# DMIC_LED.net
KiCad netlist of a schematic drawn in Altium Designer
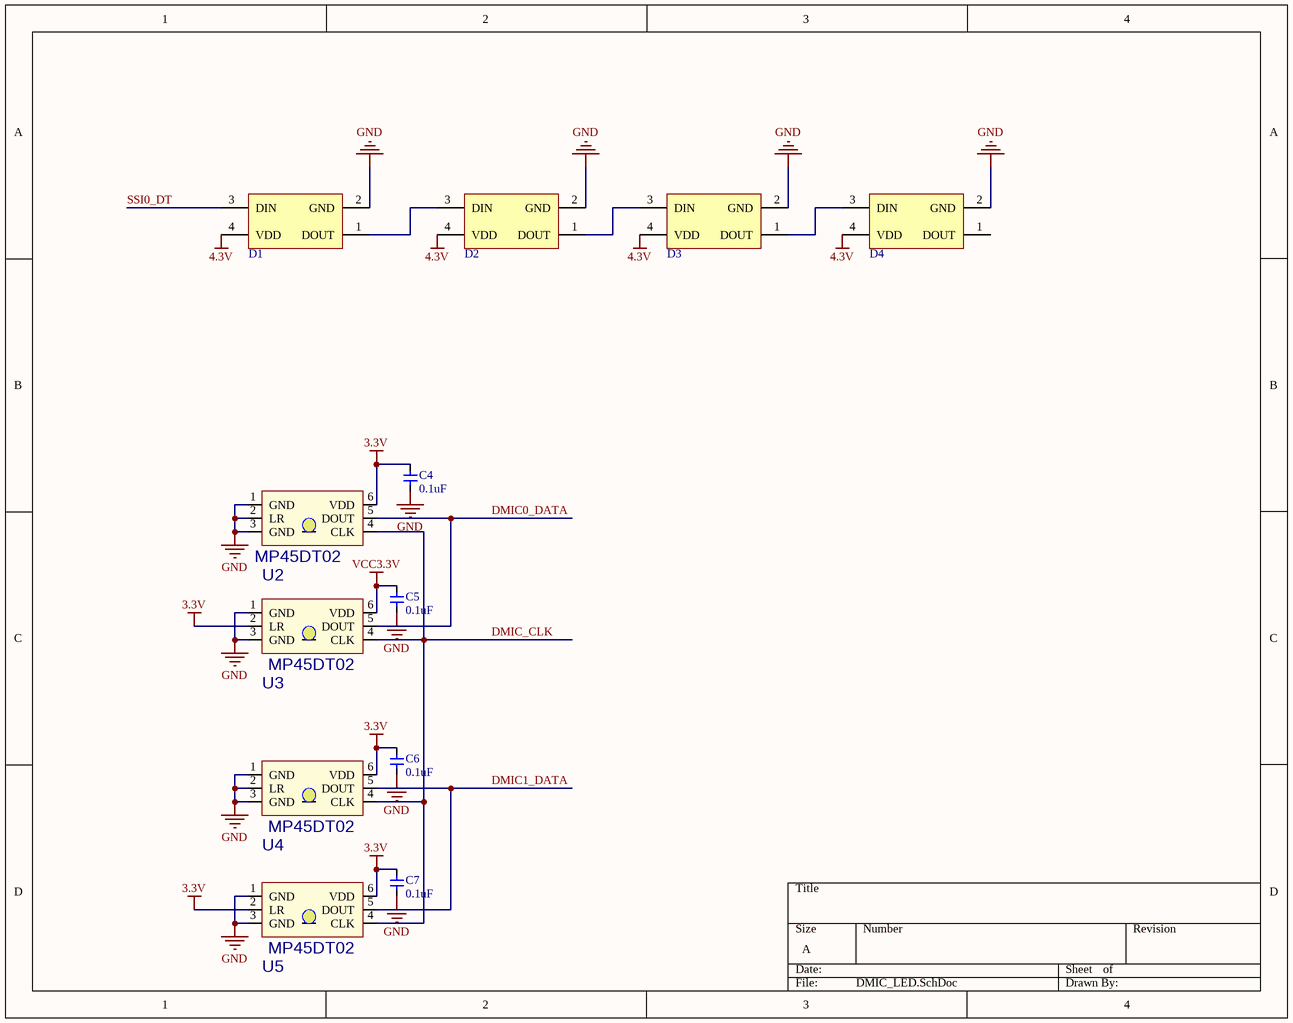
[diagram p0: DMIC_LED.SchDoc]

(export (version "E")
  (design (tool "Eeschema 10.0.6"))
  (components
    (comp (ref "C4")
      (value "0.1uF")
      (footprint "PCB_PassiveCap:CAP_0603")
      (description "Capacitor")
      (fields (field (name "Comment") "Cap_0603"))
      (libsource (lib "SCH_Passive") (part "Cap_0603"))
    )
    (comp (ref "C5")
      (value "0.1uF")
      (footprint "PCB_PassiveCap:CAP_0603")
      (description "Capacitor")
      (fields (field (name "Comment") "Cap_0603"))
      (libsource (lib "SCH_Passive") (part "Cap_0603"))
    )
    (comp (ref "C6")
      (value "0.1uF")
      (footprint "PCB_PassiveCap:CAP_0603")
      (description "Capacitor")
      (fields (field (name "Comment") "Cap_0603"))
      (libsource (lib "SCH_Passive") (part "Cap_0603"))
    )
    (comp (ref "C7")
      (value "0.1uF")
      (footprint "PCB_PassiveCap:CAP_0603")
      (description "Capacitor")
      (fields (field (name "Comment") "Cap_0603"))
      (libsource (lib "SCH_Passive") (part "Cap_0603"))
    )
    (comp (ref "D1")
      (value "LED_3535_SK6812")
      (footprint "PCB_ActiveLED:LED_3535_4P")
      (description "LED")
      (libsource (lib "SCH_Active") (part "LED_3535_SK6812"))
    )
    (comp (ref "D2")
      (value "LED_3535_SK6812")
      (footprint "PCB_ActiveLED:LED_3535_4P")
      (description "LED")
      (libsource (lib "SCH_Active") (part "LED_3535_SK6812"))
    )
    (comp (ref "D3")
      (value "LED_3535_SK6812")
      (footprint "PCB_ActiveLED:LED_3535_4P")
      (description "LED")
      (libsource (lib "SCH_Active") (part "LED_3535_SK6812"))
    )
    (comp (ref "D4")
      (value "LED_3535_SK6812")
      (footprint "PCB_ActiveLED:LED_3535_4P")
      (description "LED")
      (libsource (lib "SCH_Active") (part "LED_3535_SK6812"))
    )
    (comp (ref "U2")
      (value "MP45DT02")
      (footprint "ST_HLGA6")
      (description "Mic Omni-Directional -26dB 3.6V Rectangular Solder Pad")
      (fields (field (name "MF") "STMicroelectronics"))
      (libsource (lib "SCH_IntegratedCircuit") (part "MP45DT02"))
    )
    (comp (ref "U3")
      (value "MP45DT02")
      (footprint "ST_HLGA6")
      (description "Mic Omni-Directional -26dB 3.6V Rectangular Solder Pad")
      (fields (field (name "MF") "STMicroelectronics"))
      (libsource (lib "SCH_IntegratedCircuit") (part "MP45DT02"))
    )
    (comp (ref "U4")
      (value "MP45DT02")
      (footprint "ST_HLGA6")
      (description "Mic Omni-Directional -26dB 3.6V Rectangular Solder Pad")
      (fields (field (name "MF") "STMicroelectronics"))
      (libsource (lib "SCH_IntegratedCircuit") (part "MP45DT02"))
    )
    (comp (ref "U5")
      (value "MP45DT02")
      (footprint "ST_HLGA6")
      (description "Mic Omni-Directional -26dB 3.6V Rectangular Solder Pad")
      (fields (field (name "MF") "STMicroelectronics"))
      (libsource (lib "SCH_IntegratedCircuit") (part "MP45DT02"))
    )
  )
  (nets
    (net (code "1") (name "/DMIC0_DATA") (class "Default")
      (node (ref "U2") (pin "5") (pinfunction "DOUT_5") (pintype "passive"))
      (node (ref "U3") (pin "5") (pinfunction "DOUT_5") (pintype "passive"))
    )
    (net (code "2") (name "/DMIC1_DATA") (class "Default")
      (node (ref "U4") (pin "5") (pinfunction "DOUT_5") (pintype "passive"))
      (node (ref "U5") (pin "5") (pinfunction "DOUT_5") (pintype "passive"))
    )
    (net (code "3") (name "/DMIC_CLK") (class "Default")
      (node (ref "U2") (pin "4") (pinfunction "CLK_4") (pintype "passive"))
      (node (ref "U3") (pin "4") (pinfunction "CLK_4") (pintype "passive"))
      (node (ref "U4") (pin "4") (pinfunction "CLK_4") (pintype "passive"))
      (node (ref "U5") (pin "4") (pinfunction "CLK_4") (pintype "passive"))
    )
    (net (code "4") (name "/SSI0_DT") (class "Default")
      (node (ref "D1") (pin "3") (pinfunction "DIN_3") (pintype "passive"))
    )
    (net (code "5") (name "3.3V") (class "Default")
      (node (ref "C4") (pin "2") (pinfunction "2_2") (pintype "passive"))
      (node (ref "C6") (pin "2") (pinfunction "2_2") (pintype "passive"))
      (node (ref "C7") (pin "2") (pinfunction "2_2") (pintype "passive"))
      (node (ref "U2") (pin "6") (pinfunction "VDD_6") (pintype "passive"))
      (node (ref "U3") (pin "2") (pinfunction "LR_2") (pintype "passive"))
      (node (ref "U4") (pin "6") (pinfunction "VDD_6") (pintype "passive"))
      (node (ref "U5") (pin "2") (pinfunction "LR_2") (pintype "passive"))
      (node (ref "U5") (pin "6") (pinfunction "VDD_6") (pintype "passive"))
    )
    (net (code "6") (name "4.3V") (class "Default")
      (node (ref "D1") (pin "4") (pinfunction "VDD_4") (pintype "passive"))
      (node (ref "D2") (pin "4") (pinfunction "VDD_4") (pintype "passive"))
      (node (ref "D3") (pin "4") (pinfunction "VDD_4") (pintype "passive"))
      (node (ref "D4") (pin "4") (pinfunction "VDD_4") (pintype "passive"))
    )
    (net (code "7") (name "GND") (class "Default")
      (node (ref "C4") (pin "1") (pinfunction "1_1") (pintype "passive"))
      (node (ref "C5") (pin "1") (pinfunction "1_1") (pintype "passive"))
      (node (ref "C6") (pin "1") (pinfunction "1_1") (pintype "passive"))
      (node (ref "C7") (pin "1") (pinfunction "1_1") (pintype "passive"))
      (node (ref "D1") (pin "2") (pinfunction "GND_2") (pintype "passive"))
      (node (ref "D2") (pin "2") (pinfunction "GND_2") (pintype "passive"))
      (node (ref "D3") (pin "2") (pinfunction "GND_2") (pintype "passive"))
      (node (ref "D4") (pin "2") (pinfunction "GND_2") (pintype "passive"))
      (node (ref "U2") (pin "1") (pinfunction "GND_1") (pintype "passive"))
      (node (ref "U2") (pin "2") (pinfunction "LR_2") (pintype "passive"))
      (node (ref "U2") (pin "3") (pinfunction "GND_3") (pintype "passive"))
      (node (ref "U3") (pin "1") (pinfunction "GND_1") (pintype "passive"))
      (node (ref "U3") (pin "3") (pinfunction "GND_3") (pintype "passive"))
      (node (ref "U4") (pin "1") (pinfunction "GND_1") (pintype "passive"))
      (node (ref "U4") (pin "2") (pinfunction "LR_2") (pintype "passive"))
      (node (ref "U4") (pin "3") (pinfunction "GND_3") (pintype "passive"))
      (node (ref "U5") (pin "1") (pinfunction "GND_1") (pintype "passive"))
      (node (ref "U5") (pin "3") (pinfunction "GND_3") (pintype "passive"))
    )
    (net (code "8") (name "Net-(D1-DOUT)") (class "Default")
      (node (ref "D1") (pin "1") (pinfunction "DOUT_1") (pintype "passive"))
      (node (ref "D2") (pin "3") (pinfunction "DIN_3") (pintype "passive"))
    )
    (net (code "9") (name "Net-(D2-DOUT)") (class "Default")
      (node (ref "D2") (pin "1") (pinfunction "DOUT_1") (pintype "passive"))
      (node (ref "D3") (pin "3") (pinfunction "DIN_3") (pintype "passive"))
    )
    (net (code "10") (name "Net-(D3-DOUT)") (class "Default")
      (node (ref "D3") (pin "1") (pinfunction "DOUT_1") (pintype "passive"))
      (node (ref "D4") (pin "3") (pinfunction "DIN_3") (pintype "passive"))
    )
    (net (code "11") (name "VCC3.3V") (class "Default")
      (node (ref "C5") (pin "2") (pinfunction "2_2") (pintype "passive"))
      (node (ref "U3") (pin "6") (pinfunction "VDD_6") (pintype "passive"))
    )
    (net (code "12") (name "unconnected-(D4-DOUT-Pad1)") (class "Default")
      (node (ref "D4") (pin "1") (pinfunction "DOUT_1") (pintype "passive"))
    )
  )
)
